# screen.net
KiCad netlist of a schematic drawn in Altium Designer
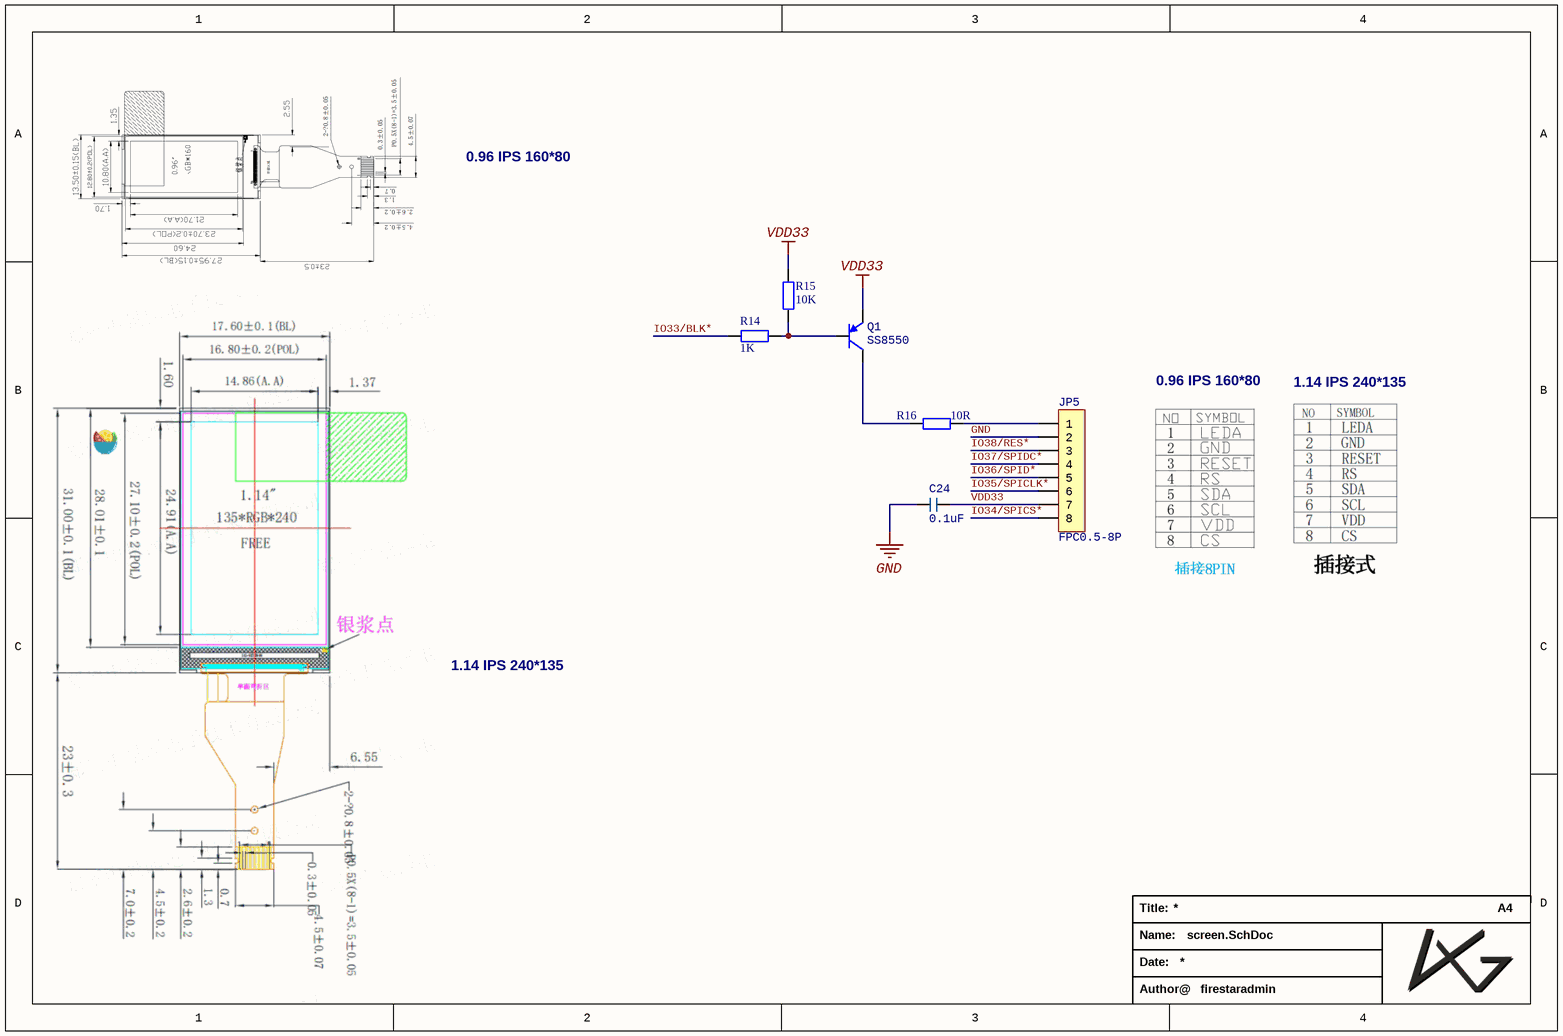
[diagram p0: screen.SchDoc]

(export (version "E")
  (design (tool "Eeschema 10.0.6"))
  (components
    (comp (ref "C24")
      (value "0.1uF")
      (footprint "C 0603_L")
      (description "无极性贴片电容")
      (fields (field (name "版权归属") "源创客"))
      (libsource (lib "SCH-电阻-电容-电感") (part "C"))
    )
    (comp (ref "JP5")
      (value "FPC0.5-8P")
      (footprint "FPC0.5 2H-WS-8P")
      (description "FPC连接器")
      (fields (field (name "版权归属") "源创客"))
      (libsource (lib "SCH-接插件-FPC") (part "FPC-8P"))
    )
    (comp (ref "Q1")
      (value "SS8550")
      (footprint "SOT23-3N")
      (description "高频放大-PNP型")
      (fields (field (name "版权归属") "源创客"))
      (libsource (lib "SCH-三极管") (part "8550-SMD"))
    )
    (comp (ref "R14")
      (value "1K")
      (footprint "R 0603_L")
      (description "贴片电阻")
      (fields (field (name "版权归属") "源创客"))
      (libsource (lib "SCH-电阻-电容-电感") (part "R"))
    )
    (comp (ref "R15")
      (value "10K")
      (footprint "R 0603_L")
      (description "贴片电阻")
      (fields (field (name "版权归属") "源创客"))
      (libsource (lib "SCH-电阻-电容-电感") (part "R"))
    )
    (comp (ref "R16")
      (value "10R")
      (footprint "R 0603_L")
      (description "贴片电阻")
      (fields (field (name "版权归属") "源创客"))
      (libsource (lib "SCH-电阻-电容-电感") (part "R"))
    )
  )
  (nets
    (net (code "1") (name "/IO33{slash}BLK*") (class "Default")
      (node (ref "R14") (pin "2") (pinfunction "2_2") (pintype "passive"))
    )
    (net (code "2") (name "/IO34{slash}SPICS*") (class "Default")
      (node (ref "JP5") (pin "8") (pinfunction "8_8") (pintype "passive"))
    )
    (net (code "3") (name "/IO35{slash}SPICLK*") (class "Default")
      (node (ref "JP5") (pin "6") (pinfunction "6_6") (pintype "passive"))
    )
    (net (code "4") (name "/IO36{slash}SPID*") (class "Default")
      (node (ref "JP5") (pin "5") (pinfunction "5_5") (pintype "passive"))
    )
    (net (code "5") (name "/IO37{slash}SPIDC*") (class "Default")
      (node (ref "JP5") (pin "4") (pinfunction "4_4") (pintype "passive"))
    )
    (net (code "6") (name "/IO38{slash}RES*") (class "Default")
      (node (ref "JP5") (pin "3") (pinfunction "3_3") (pintype "passive"))
    )
    (net (code "7") (name "GND") (class "Default")
      (node (ref "C24") (pin "1") (pinfunction "1_1") (pintype "passive"))
      (node (ref "JP5") (pin "2") (pinfunction "2_2") (pintype "passive"))
    )
    (net (code "8") (name "Net-(JP5-Pad1)") (class "Default")
      (node (ref "JP5") (pin "1") (pinfunction "1_1") (pintype "passive"))
      (node (ref "R16") (pin "1") (pinfunction "1_1") (pintype "passive"))
    )
    (net (code "9") (name "Net-(Q1-B)") (class "Default")
      (node (ref "Q1") (pin "1") (pinfunction "B_1") (pintype "passive"))
      (node (ref "R14") (pin "1") (pinfunction "1_1") (pintype "passive"))
      (node (ref "R15") (pin "1") (pinfunction "1_1") (pintype "passive"))
    )
    (net (code "10") (name "Net-(Q1-C)") (class "Default")
      (node (ref "Q1") (pin "3") (pinfunction "C_3") (pintype "passive"))
      (node (ref "R16") (pin "2") (pinfunction "2_2") (pintype "passive"))
    )
    (net (code "11") (name "VDD33") (class "Default")
      (node (ref "C24") (pin "2") (pinfunction "2_2") (pintype "passive"))
      (node (ref "JP5") (pin "7") (pinfunction "7_7") (pintype "passive"))
      (node (ref "Q1") (pin "2") (pinfunction "E_2") (pintype "passive"))
      (node (ref "R15") (pin "2") (pinfunction "2_2") (pintype "passive"))
    )
  )
)
